# home_automation.net
KiCad netlist of a schematic drawn in EAGLE
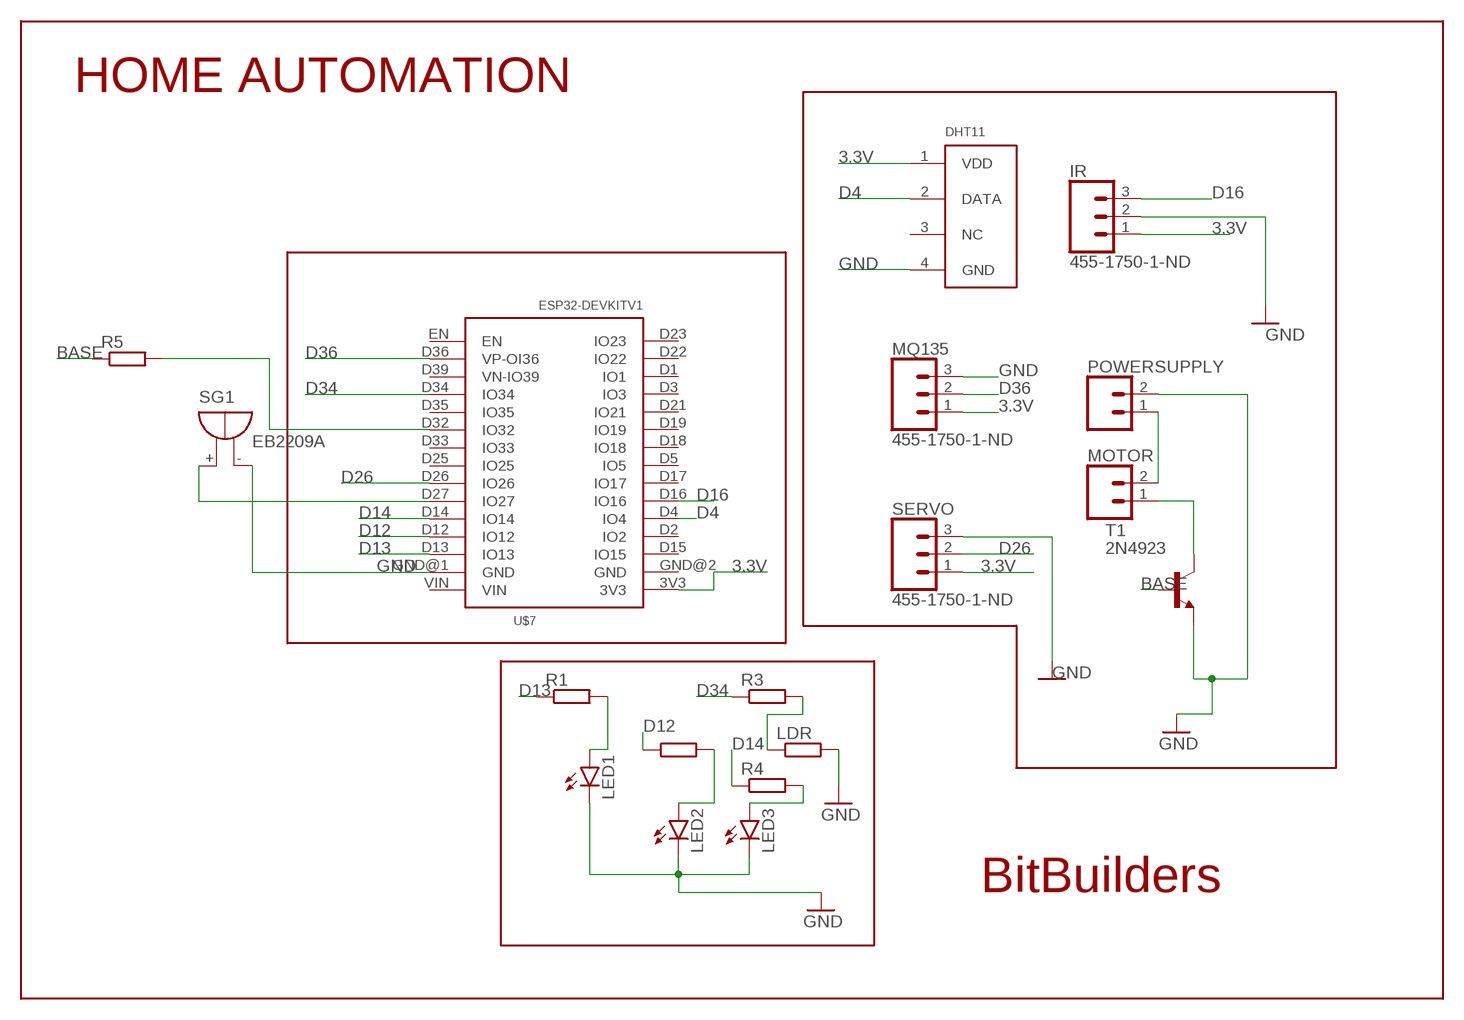
[diagram p0: schematic, sheet 1]

(export (version "E")
  (design (tool "Eeschema 10.0.6"))
  (components
    (comp (ref "DHT11")
      (value "DHT11")
      (footprint "eagle-import:DHT11")
      (libsource (lib "eagle-import") (part "DHT11"))
    )
    (comp (ref "IR")
      (value "455-1750-1-ND")
      (footprint "eagle-import:1X03")
      (libsource (lib "eagle-import") (part "CONN_03"))
    )
    (comp (ref "LDR")
      (value "R-EU_0204/7")
      (footprint "eagle-import:0204_7")
      (libsource (lib "eagle-import") (part "R-EU_0204/7"))
    )
    (comp (ref "LED1")
      (value "LED5MM")
      (footprint "eagle-import:LED5MM")
      (libsource (lib "eagle-import") (part "LED5MM"))
    )
    (comp (ref "LED2")
      (value "LED5MM")
      (footprint "eagle-import:LED5MM")
      (libsource (lib "eagle-import") (part "LED5MM"))
    )
    (comp (ref "LED3")
      (value "LED5MM")
      (footprint "eagle-import:LED5MM")
      (libsource (lib "eagle-import") (part "LED5MM"))
    )
    (comp (ref "MOTOR")
      (value "CONN_02")
      (footprint "eagle-import:1X02")
      (libsource (lib "eagle-import") (part "CONN_02"))
    )
    (comp (ref "MQ135")
      (value "455-1750-1-ND")
      (footprint "eagle-import:1X03")
      (libsource (lib "eagle-import") (part "CONN_03"))
    )
    (comp (ref "POWERSUPPLY")
      (value "CONN_02")
      (footprint "eagle-import:1X02")
      (libsource (lib "eagle-import") (part "CONN_02"))
    )
    (comp (ref "R1")
      (value "R-EU_0204/5")
      (footprint "eagle-import:0204_5")
      (libsource (lib "eagle-import") (part "R-EU_0204/5"))
    )
    (comp (ref "R2")
      (value "R-EU_0204/5")
      (footprint "eagle-import:0204_5")
      (libsource (lib "eagle-import") (part "R-EU_0204/5"))
    )
    (comp (ref "R3")
      (value "R-EU_0204/5")
      (footprint "eagle-import:0204_5")
      (libsource (lib "eagle-import") (part "R-EU_0204/5"))
    )
    (comp (ref "R4")
      (value "R-EU_0204/7")
      (footprint "eagle-import:0204_7")
      (libsource (lib "eagle-import") (part "R-EU_0204/7"))
    )
    (comp (ref "R5")
      (value "R-EU_0204/7")
      (footprint "eagle-import:0204_7")
      (libsource (lib "eagle-import") (part "R-EU_0204/7"))
    )
    (comp (ref "SERVO")
      (value "455-1750-1-ND")
      (footprint "eagle-import:1X03")
      (libsource (lib "eagle-import") (part "CONN_03"))
    )
    (comp (ref "SG1")
      (value "EB2209A")
      (footprint "eagle-import:EB2209A")
      (libsource (lib "eagle-import") (part "EB2209A"))
    )
    (comp (ref "T1")
      (value "2N4923")
      (footprint "eagle-import:TO126")
      (libsource (lib "eagle-import") (part "2N4923"))
    )
    (comp (ref "U$7")
      (value "ESP32DEVKITV1")
      (footprint "eagle-import:ESP32-DEVKITV1")
      (libsource (lib "eagle-import") (part "ESP32DEVKITV1"))
    )
  )
  (nets
    (net (code "1") (name "/3.3V") (class "Default")
      (node (ref "DHT11") (pin "1") (pinfunction "VDD_1") (pintype "power_in"))
      (node (ref "IR") (pin "1") (pinfunction "1_1") (pintype "passive"))
      (node (ref "MQ135") (pin "1") (pinfunction "1_1") (pintype "passive"))
      (node (ref "SERVO") (pin "1") (pinfunction "1_1") (pintype "passive"))
      (node (ref "U$7") (pin "3V3") (pinfunction "3V3_3V3") (pintype "bidirectional"))
    )
    (net (code "2") (name "/BASE") (class "Default")
      (node (ref "R5") (pin "1") (pinfunction "1_1") (pintype "passive"))
      (node (ref "T1") (pin "3") (pinfunction "B_3") (pintype "passive"))
    )
    (net (code "3") (name "/D4") (class "Default")
      (node (ref "DHT11") (pin "2") (pinfunction "DATA_2") (pintype "bidirectional"))
      (node (ref "U$7") (pin "D4") (pinfunction "IO4_D4") (pintype "bidirectional"))
    )
    (net (code "4") (name "/D12") (class "Default")
      (node (ref "R2") (pin "1") (pinfunction "1_1") (pintype "passive"))
      (node (ref "U$7") (pin "D12") (pinfunction "IO12_D12") (pintype "bidirectional"))
    )
    (net (code "5") (name "/D13") (class "Default")
      (node (ref "R1") (pin "1") (pinfunction "1_1") (pintype "passive"))
      (node (ref "U$7") (pin "D13") (pinfunction "IO13_D13") (pintype "bidirectional"))
    )
    (net (code "6") (name "/D14") (class "Default")
      (node (ref "R4") (pin "1") (pinfunction "1_1") (pintype "passive"))
      (node (ref "U$7") (pin "D14") (pinfunction "IO14_D14") (pintype "bidirectional"))
    )
    (net (code "7") (name "/D16") (class "Default")
      (node (ref "IR") (pin "3") (pinfunction "3_3") (pintype "passive"))
      (node (ref "U$7") (pin "D16") (pinfunction "IO16_D16") (pintype "bidirectional"))
    )
    (net (code "8") (name "/D26") (class "Default")
      (node (ref "SERVO") (pin "2") (pinfunction "2_2") (pintype "passive"))
      (node (ref "U$7") (pin "D26") (pinfunction "IO26_D26") (pintype "bidirectional"))
    )
    (net (code "9") (name "/D34") (class "Default")
      (node (ref "R3") (pin "1") (pinfunction "1_1") (pintype "passive"))
      (node (ref "U$7") (pin "D34") (pinfunction "IO34_D34") (pintype "bidirectional"))
    )
    (net (code "10") (name "/D36") (class "Default")
      (node (ref "MQ135") (pin "2") (pinfunction "2_2") (pintype "passive"))
      (node (ref "U$7") (pin "D36") (pinfunction "VP-OI36_D36") (pintype "bidirectional"))
    )
    (net (code "11") (name "GND") (class "Default")
      (node (ref "DHT11") (pin "4") (pinfunction "GND_4") (pintype "power_in"))
      (node (ref "IR") (pin "2") (pinfunction "2_2") (pintype "passive"))
      (node (ref "LDR") (pin "2") (pinfunction "2_2") (pintype "passive"))
      (node (ref "LED1") (pin "K") (pinfunction "C_K") (pintype "passive"))
      (node (ref "LED2") (pin "K") (pinfunction "C_K") (pintype "passive"))
      (node (ref "LED3") (pin "K") (pinfunction "C_K") (pintype "passive"))
      (node (ref "MQ135") (pin "3") (pinfunction "3_3") (pintype "passive"))
      (node (ref "POWERSUPPLY") (pin "2") (pinfunction "2_2") (pintype "passive"))
      (node (ref "SERVO") (pin "3") (pinfunction "3_3") (pintype "passive"))
      (node (ref "SG1") (pin "-") (pinfunction "-_-") (pintype "passive"))
      (node (ref "T1") (pin "1") (pinfunction "E_1") (pintype "passive"))
      (node (ref "U$7") (pin "GND@1") (pinfunction "GND_GND@1") (pintype "bidirectional"))
    )
    (net (code "12") (name "Net-(LDR-Pad1)") (class "Default")
      (node (ref "LDR") (pin "1") (pinfunction "1_1") (pintype "passive"))
      (node (ref "R3") (pin "2") (pinfunction "2_2") (pintype "passive"))
    )
    (net (code "13") (name "Net-(LED1-PadA)") (class "Default")
      (node (ref "LED1") (pin "A") (pinfunction "A_A") (pintype "passive"))
      (node (ref "R1") (pin "2") (pinfunction "2_2") (pintype "passive"))
    )
    (net (code "14") (name "Net-(LED2-PadA)") (class "Default")
      (node (ref "LED2") (pin "A") (pinfunction "A_A") (pintype "passive"))
      (node (ref "R2") (pin "2") (pinfunction "2_2") (pintype "passive"))
    )
    (net (code "15") (name "Net-(LED3-PadA)") (class "Default")
      (node (ref "LED3") (pin "A") (pinfunction "A_A") (pintype "passive"))
      (node (ref "R4") (pin "2") (pinfunction "2_2") (pintype "passive"))
    )
    (net (code "16") (name "Net-(MOTOR-Pad2)") (class "Default")
      (node (ref "MOTOR") (pin "2") (pinfunction "2_2") (pintype "passive"))
      (node (ref "POWERSUPPLY") (pin "1") (pinfunction "1_1") (pintype "passive"))
    )
    (net (code "17") (name "Net-(T1-C)") (class "Default")
      (node (ref "MOTOR") (pin "1") (pinfunction "1_1") (pintype "passive"))
      (node (ref "T1") (pin "2") (pinfunction "C_2") (pintype "passive"))
    )
    (net (code "18") (name "Net-(U$7-IO27)") (class "Default")
      (node (ref "SG1") (pin "+") (pinfunction "+_+") (pintype "passive"))
      (node (ref "U$7") (pin "D27") (pinfunction "IO27_D27") (pintype "bidirectional"))
    )
    (net (code "19") (name "Net-(U$7-IO32)") (class "Default")
      (node (ref "R5") (pin "2") (pinfunction "2_2") (pintype "passive"))
      (node (ref "U$7") (pin "D32") (pinfunction "IO32_D32") (pintype "bidirectional"))
    )
    (net (code "20") (name "unconnected-(DHT11-NC-Pad3)") (class "Default")
      (node (ref "DHT11") (pin "3") (pinfunction "NC_3") (pintype "bidirectional"))
    )
    (net (code "21") (name "unconnected-(U$7-GND-PadGND@2)") (class "Default")
      (node (ref "U$7") (pin "GND@2") (pinfunction "GND_GND@2") (pintype "bidirectional"))
    )
    (net (code "22") (name "unconnected-(U$7-IO1-PadD1)") (class "Default")
      (node (ref "U$7") (pin "D1") (pinfunction "IO1_D1") (pintype "bidirectional"))
    )
    (net (code "23") (name "unconnected-(U$7-IO2-PadD2)") (class "Default")
      (node (ref "U$7") (pin "D2") (pinfunction "IO2_D2") (pintype "bidirectional"))
    )
    (net (code "24") (name "unconnected-(U$7-IO3-PadD3)") (class "Default")
      (node (ref "U$7") (pin "D3") (pinfunction "IO3_D3") (pintype "bidirectional"))
    )
    (net (code "25") (name "unconnected-(U$7-IO5-PadD5)") (class "Default")
      (node (ref "U$7") (pin "D5") (pinfunction "IO5_D5") (pintype "bidirectional"))
    )
    (net (code "26") (name "unconnected-(U$7-IO15-PadD15)") (class "Default")
      (node (ref "U$7") (pin "D15") (pinfunction "IO15_D15") (pintype "bidirectional"))
    )
    (net (code "27") (name "unconnected-(U$7-IO17-PadD17)") (class "Default")
      (node (ref "U$7") (pin "D17") (pinfunction "IO17_D17") (pintype "bidirectional"))
    )
    (net (code "28") (name "unconnected-(U$7-IO18-PadD18)") (class "Default")
      (node (ref "U$7") (pin "D18") (pinfunction "IO18_D18") (pintype "bidirectional"))
    )
    (net (code "29") (name "unconnected-(U$7-IO19-PadD19)") (class "Default")
      (node (ref "U$7") (pin "D19") (pinfunction "IO19_D19") (pintype "bidirectional"))
    )
    (net (code "30") (name "unconnected-(U$7-IO21-PadD21)") (class "Default")
      (node (ref "U$7") (pin "D21") (pinfunction "IO21_D21") (pintype "bidirectional"))
    )
    (net (code "31") (name "unconnected-(U$7-IO22-PadD22)") (class "Default")
      (node (ref "U$7") (pin "D22") (pinfunction "IO22_D22") (pintype "bidirectional"))
    )
    (net (code "32") (name "unconnected-(U$7-IO23-PadD23)") (class "Default")
      (node (ref "U$7") (pin "D23") (pinfunction "IO23_D23") (pintype "bidirectional"))
    )
    (net (code "33") (name "unconnected-(U$7-IO25-PadD25)") (class "Default")
      (node (ref "U$7") (pin "D25") (pinfunction "IO25_D25") (pintype "bidirectional"))
    )
    (net (code "34") (name "unconnected-(U$7-IO33-PadD33)") (class "Default")
      (node (ref "U$7") (pin "D33") (pinfunction "IO33_D33") (pintype "bidirectional"))
    )
    (net (code "35") (name "unconnected-(U$7-IO35-PadD35)") (class "Default")
      (node (ref "U$7") (pin "D35") (pinfunction "IO35_D35") (pintype "bidirectional"))
    )
    (net (code "36") (name "unconnected-(U$7-PadEN)") (class "Default")
      (node (ref "U$7") (pin "EN") (pinfunction "EN_EN") (pintype "bidirectional"))
    )
    (net (code "37") (name "unconnected-(U$7-PadVIN)") (class "Default")
      (node (ref "U$7") (pin "VIN") (pinfunction "VIN_VIN") (pintype "bidirectional"))
    )
    (net (code "38") (name "unconnected-(U$7-VN-IO39-PadD39)") (class "Default")
      (node (ref "U$7") (pin "D39") (pinfunction "VN-IO39_D39") (pintype "bidirectional"))
    )
  )
)
